# MRCS-RJ45-CMRI.net
KiCad netlist of a schematic drawn in EAGLE
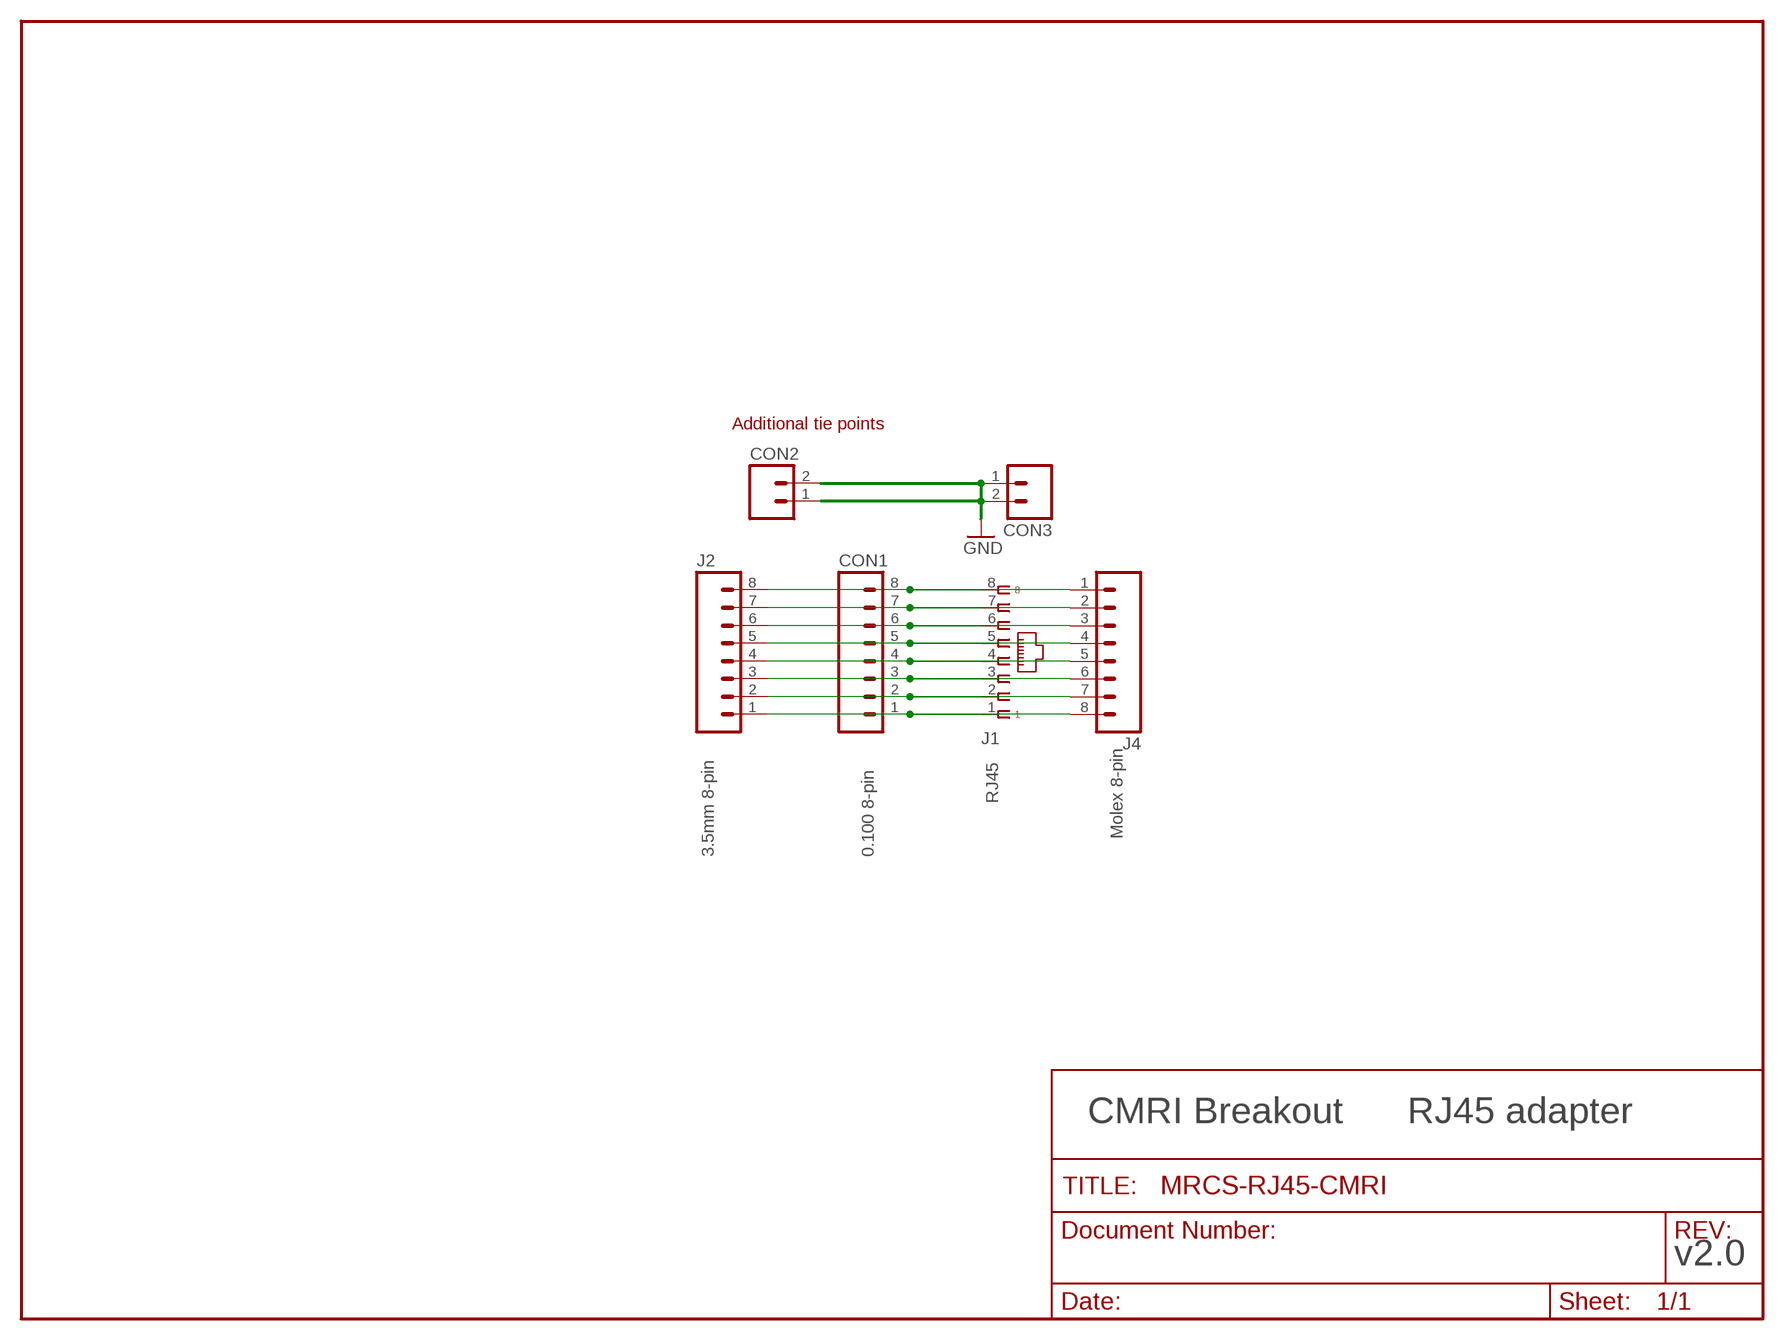
[diagram p0: schematic, sheet 1]

(export (version "E")
  (design (tool "Eeschema 10.0.6"))
  (components
    (comp (ref "CON1")
      (value "CONNECTOR-M08LOCK")
      (footprint "eagle-import:1X08_LOCK")
      (libsource (lib "eagle-import") (part "CONNECTOR-M08LOCK"))
    )
    (comp (ref "CON2")
      (value "CONNECTOR-M023.5MM-LOCK")
      (footprint "eagle-import:SCREWTERMINAL-3.5MM-2_LOCK")
      (libsource (lib "eagle-import") (part "CONNECTOR-M023.5MM-LOCK"))
    )
    (comp (ref "CON3")
      (value "CONNECTOR-M023.5MM-LOCK")
      (footprint "eagle-import:SCREWTERMINAL-3.5MM-2_LOCK")
      (libsource (lib "eagle-import") (part "CONNECTOR-M023.5MM-LOCK"))
    )
    (comp (ref "J1")
      (value "CONNECTOR-RJ45-FRONT")
      (footprint "eagle-import:RJ45-NO-SHIELD")
      (libsource (lib "eagle-import") (part "CONNECTOR-RJ45-FRONT"))
    )
    (comp (ref "J2")
      (value "CONNECTOR-M083.5MM-8")
      (footprint "eagle-import:SCREWTERMINAL-3.5MM-8")
      (libsource (lib "eagle-import") (part "CONNECTOR-M083.5MM-8"))
    )
    (comp (ref "J4")
      (value "CONNECTOR-M081.56-F")
      (footprint "eagle-import:KK-156-8-F")
      (libsource (lib "eagle-import") (part "CONNECTOR-M081.56-F"))
    )
  )
  (nets
    (net (code "1") (name "GND") (class "Default")
      (node (ref "CON2") (pin "1") (pinfunction "A_1") (pintype "passive"))
      (node (ref "CON2") (pin "2") (pinfunction "B_2") (pintype "passive"))
      (node (ref "CON3") (pin "1") (pinfunction "A_1") (pintype "passive"))
      (node (ref "CON3") (pin "2") (pinfunction "B_2") (pintype "passive"))
    )
    (net (code "2") (name "Net-(CON1-Pad1)") (class "Default")
      (node (ref "CON1") (pin "1") (pinfunction "1_1") (pintype "passive"))
      (node (ref "J1") (pin "1") (pinfunction "1_1") (pintype "passive"))
      (node (ref "J2") (pin "1") (pinfunction "1_1") (pintype "passive"))
      (node (ref "J4") (pin "8") (pinfunction "8_8") (pintype "passive"))
    )
    (net (code "3") (name "Net-(CON1-Pad2)") (class "Default")
      (node (ref "CON1") (pin "2") (pinfunction "2_2") (pintype "passive"))
      (node (ref "J1") (pin "2") (pinfunction "2_2") (pintype "passive"))
      (node (ref "J2") (pin "2") (pinfunction "2_2") (pintype "passive"))
      (node (ref "J4") (pin "7") (pinfunction "7_7") (pintype "passive"))
    )
    (net (code "4") (name "Net-(CON1-Pad3)") (class "Default")
      (node (ref "CON1") (pin "3") (pinfunction "3_3") (pintype "passive"))
      (node (ref "J1") (pin "3") (pinfunction "3_3") (pintype "passive"))
      (node (ref "J2") (pin "3") (pinfunction "3_3") (pintype "passive"))
      (node (ref "J4") (pin "6") (pinfunction "6_6") (pintype "passive"))
    )
    (net (code "5") (name "Net-(CON1-Pad4)") (class "Default")
      (node (ref "CON1") (pin "4") (pinfunction "4_4") (pintype "passive"))
      (node (ref "J1") (pin "4") (pinfunction "4_4") (pintype "passive"))
      (node (ref "J2") (pin "4") (pinfunction "4_4") (pintype "passive"))
      (node (ref "J4") (pin "5") (pinfunction "5_5") (pintype "passive"))
    )
    (net (code "6") (name "Net-(CON1-Pad5)") (class "Default")
      (node (ref "CON1") (pin "5") (pinfunction "5_5") (pintype "passive"))
      (node (ref "J1") (pin "5") (pinfunction "5_5") (pintype "passive"))
      (node (ref "J2") (pin "5") (pinfunction "5_5") (pintype "passive"))
      (node (ref "J4") (pin "4") (pinfunction "4_4") (pintype "passive"))
    )
    (net (code "7") (name "Net-(CON1-Pad6)") (class "Default")
      (node (ref "CON1") (pin "6") (pinfunction "6_6") (pintype "passive"))
      (node (ref "J1") (pin "6") (pinfunction "6_6") (pintype "passive"))
      (node (ref "J2") (pin "6") (pinfunction "6_6") (pintype "passive"))
      (node (ref "J4") (pin "3") (pinfunction "3_3") (pintype "passive"))
    )
    (net (code "8") (name "Net-(CON1-Pad7)") (class "Default")
      (node (ref "CON1") (pin "7") (pinfunction "7_7") (pintype "passive"))
      (node (ref "J1") (pin "7") (pinfunction "7_7") (pintype "passive"))
      (node (ref "J2") (pin "7") (pinfunction "7_7") (pintype "passive"))
      (node (ref "J4") (pin "2") (pinfunction "2_2") (pintype "passive"))
    )
    (net (code "9") (name "Net-(CON1-Pad8)") (class "Default")
      (node (ref "CON1") (pin "8") (pinfunction "8_8") (pintype "passive"))
      (node (ref "J1") (pin "8") (pinfunction "8_8") (pintype "passive"))
      (node (ref "J2") (pin "8") (pinfunction "8_8") (pintype "passive"))
      (node (ref "J4") (pin "1") (pinfunction "1_1") (pintype "passive"))
    )
  )
)
